# Bpod_Controller_v5.net
KiCad netlist of a schematic drawn in Altium Designer
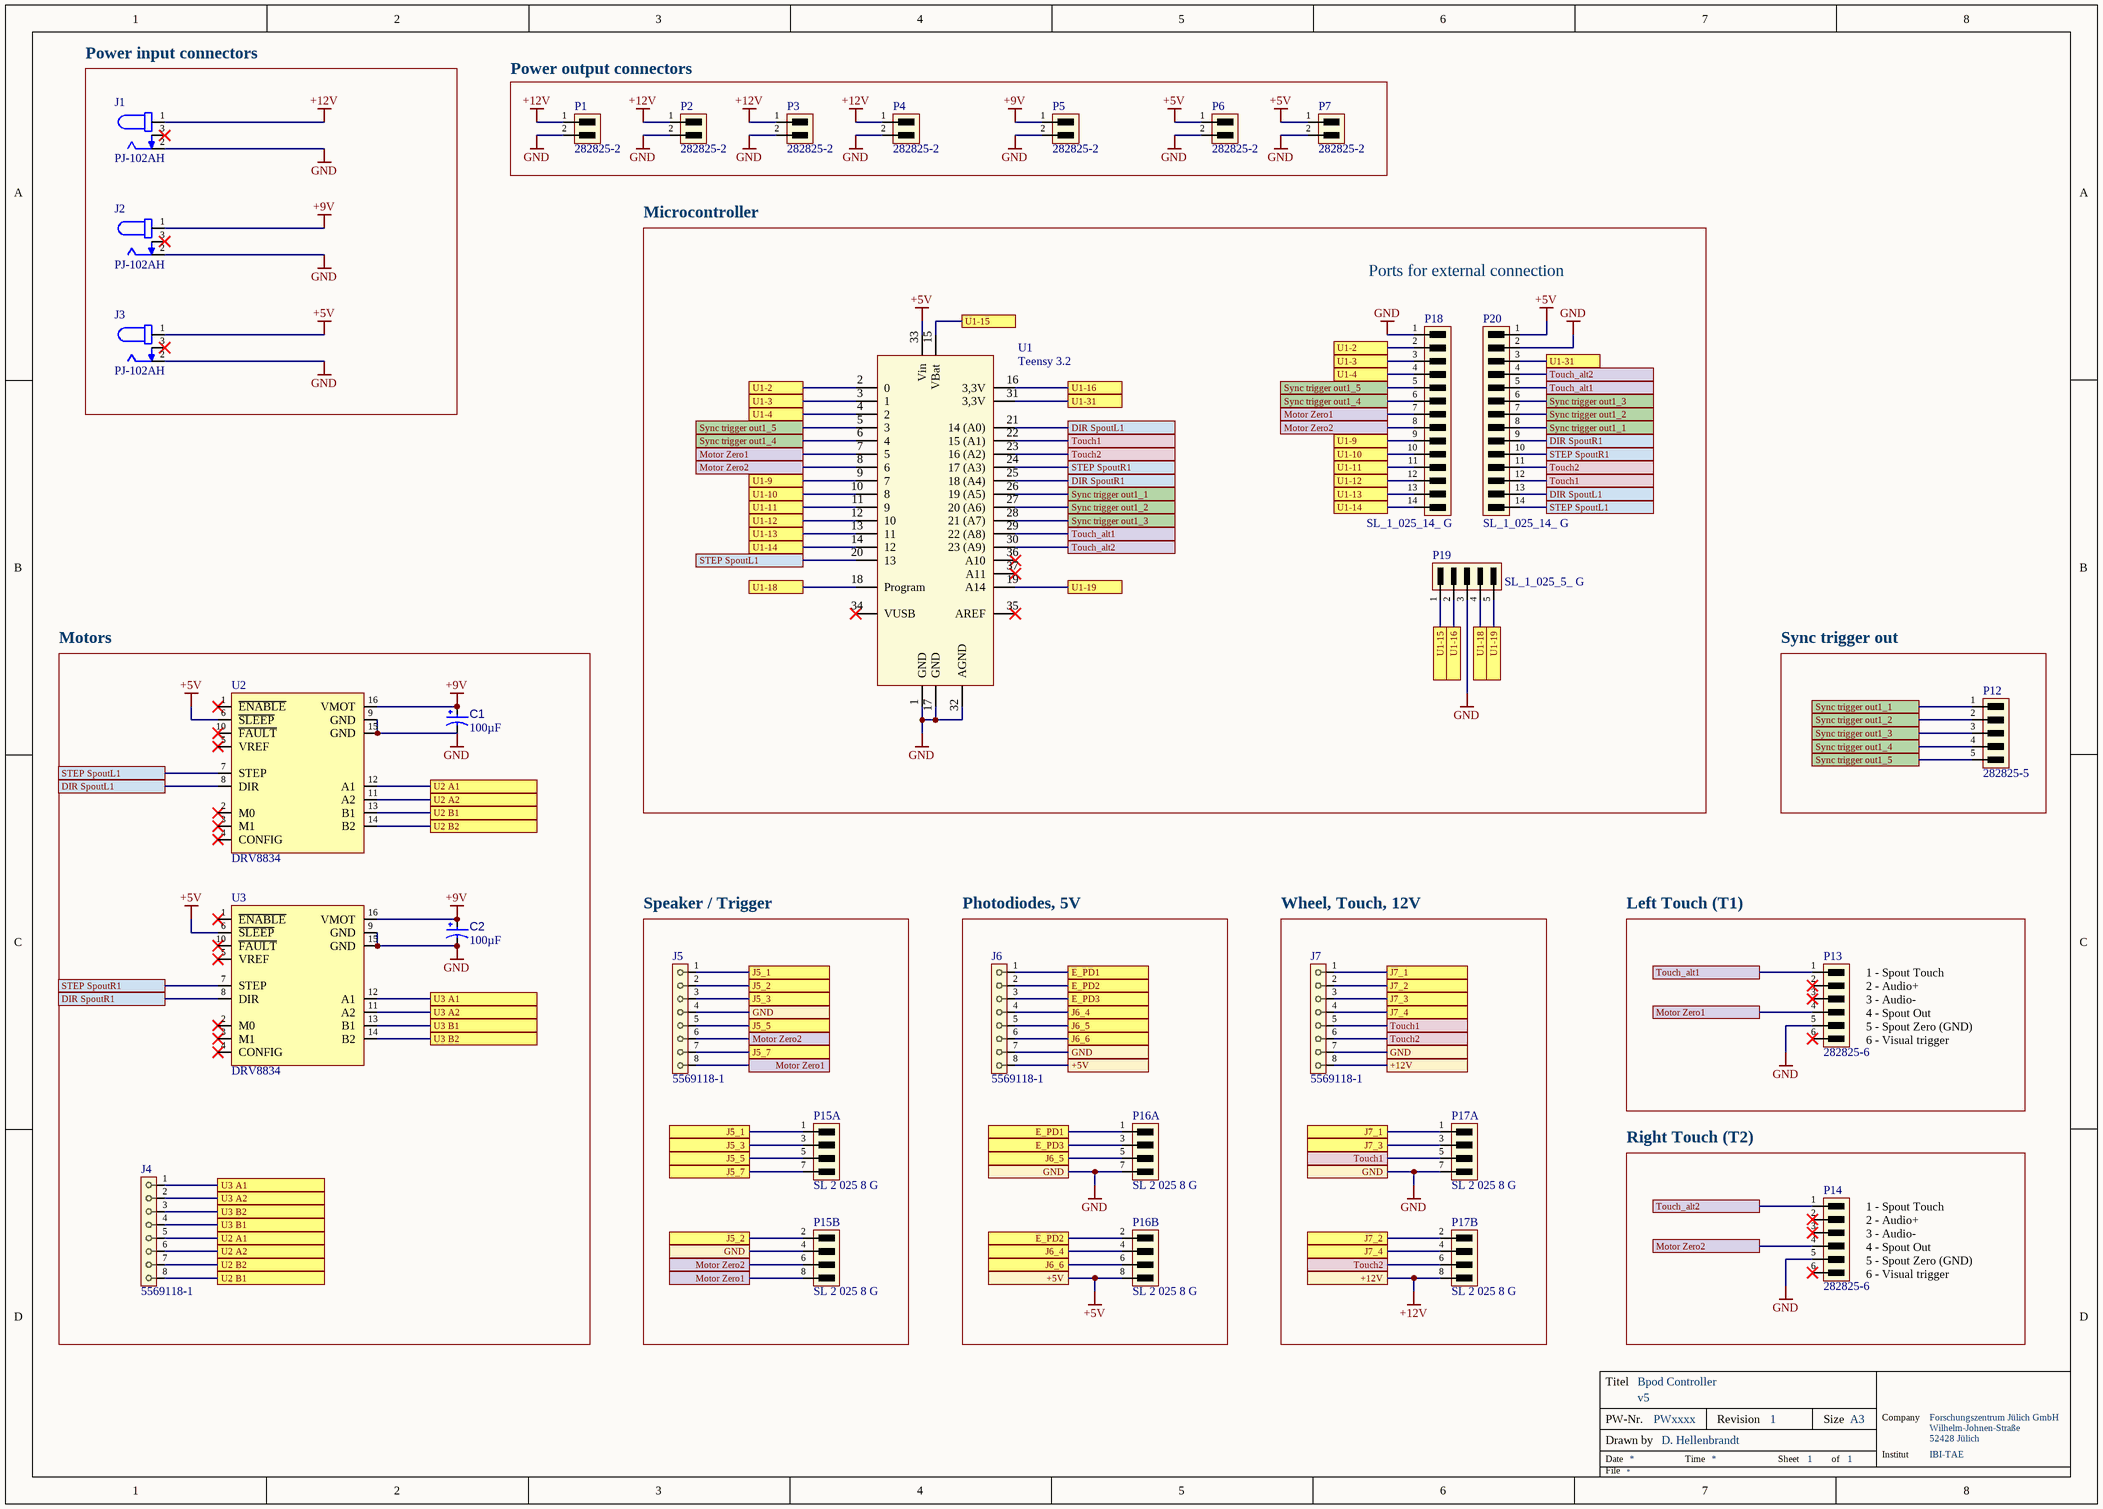
[diagram p0: Bpod_Controller_v5.SchDoc]

(export (version "E")
  (design (tool "Eeschema 10.0.6"))
  (components
    (comp (ref "C1")
      (value "100µF")
      (footprint "AVX-TAJ-C-2_M")
      (description "Standard Tantalum, 100 uF, +/- 10%, 16 V, -55 to 125 degC, 2312 (6032 Metric), RoHS, Tape and Reel")
      (fields (field (name "TOLERANCE") "10%") (field (name "MANUFACTURER") "AVX"))
      (libsource (lib "") (part "CAP-P-2_1"))
    )
    (comp (ref "C2")
      (value "100µF")
      (footprint "AVX-TAJ-C-2_M")
      (description "Standard Tantalum, 100 uF, +/- 10%, 16 V, -55 to 125 degC, 2312 (6032 Metric), RoHS, Tape and Reel")
      (fields (field (name "TOLERANCE") "10%") (field (name "MANUFACTURER") "AVX"))
      (libsource (lib "Forschungszentrum Jülich GmbH") (part "CAP-P-2"))
    )
    (comp (ref "J1")
      (value "PJ-102AH")
      (footprint "CUI_PJ-102AH")
      (description "12V, 2.5A, 2mm Dia")
      (fields (field (name "USER") "IBI-TAE"))
      (libsource (lib "Forschungszentrum Jülich GmbH") (part "PJ-102AH"))
    )
    (comp (ref "J2")
      (value "PJ-102AH")
      (footprint "CUI_PJ-102AH")
      (description "12V, 2.5A, 2mm Dia")
      (fields (field (name "USER") "IBI-TAE"))
      (libsource (lib "Forschungszentrum Jülich GmbH") (part "PJ-102AH"))
    )
    (comp (ref "J3")
      (value "PJ-102AH")
      (footprint "CUI_PJ-102AH")
      (description "12V, 2.5A, 2mm Dia")
      (fields (field (name "USER") "IBI-TAE"))
      (libsource (lib "Forschungszentrum Jülich GmbH") (part "PJ-102AH"))
    )
    (comp (ref "J4")
      (value "5569118-1")
      (footprint "5569118-1-Footprint-1")
      (description "Telecom and Datacom Connector, 8 Contact(s), Female, Right Angle, Solder Terminal, Locking, Jack")
      (fields (field (name "USER") "IBI-TAE"))
      (libsource (lib "Forschungszentrum Jülich GmbH") (part "5569118-1"))
    )
    (comp (ref "J5")
      (value "5569118-1")
      (footprint "5569118-1-Footprint-1")
      (description "Telecom and Datacom Connector, 8 Contact(s), Female, Right Angle, Solder Terminal, Locking, Jack")
      (fields (field (name "USER") "IBI-TAE"))
      (libsource (lib "Forschungszentrum Jülich GmbH") (part "5569118-1"))
    )
    (comp (ref "J6")
      (value "5569118-1")
      (footprint "5569118-1-Footprint-1")
      (description "Telecom and Datacom Connector, 8 Contact(s), Female, Right Angle, Solder Terminal, Locking, Jack")
      (fields (field (name "USER") "IBI-TAE"))
      (libsource (lib "Forschungszentrum Jülich GmbH") (part "5569118-1"))
    )
    (comp (ref "J7")
      (value "5569118-1")
      (footprint "5569118-1-Footprint-1")
      (description "Telecom and Datacom Connector, 8 Contact(s), Female, Right Angle, Solder Terminal, Locking, Jack")
      (fields (field (name "USER") "IBI-TAE"))
      (libsource (lib "Forschungszentrum Jülich GmbH") (part "5569118-1"))
    )
    (comp (ref "P1")
      (value "282825-2")
      (footprint "282825-4-Footprint-1")
      (description "Strip Terminal Block, 15A, 1 Row(s), 1 Deck(s)")
      (fields (field (name "USER") "IBI-TAE"))
      (libsource (lib "Forschungszentrum Jülich GmbH") (part "282825-2"))
    )
    (comp (ref "P2")
      (value "282825-2")
      (footprint "282825-4-Footprint-1")
      (description "Strip Terminal Block, 15A, 1 Row(s), 1 Deck(s)")
      (fields (field (name "USER") "IBI-TAE"))
      (libsource (lib "Forschungszentrum Jülich GmbH") (part "282825-2"))
    )
    (comp (ref "P3")
      (value "282825-2")
      (footprint "282825-4-Footprint-1")
      (description "Strip Terminal Block, 15A, 1 Row(s), 1 Deck(s)")
      (fields (field (name "USER") "IBI-TAE"))
      (libsource (lib "Forschungszentrum Jülich GmbH") (part "282825-2"))
    )
    (comp (ref "P4")
      (value "282825-2")
      (footprint "282825-4-Footprint-1")
      (description "Strip Terminal Block, 15A, 1 Row(s), 1 Deck(s)")
      (fields (field (name "USER") "IBI-TAE"))
      (libsource (lib "Forschungszentrum Jülich GmbH") (part "282825-2"))
    )
    (comp (ref "P5")
      (value "282825-2")
      (footprint "282825-4-Footprint-1")
      (description "Strip Terminal Block, 15A, 1 Row(s), 1 Deck(s)")
      (fields (field (name "USER") "IBI-TAE"))
      (libsource (lib "Forschungszentrum Jülich GmbH") (part "282825-2"))
    )
    (comp (ref "P6")
      (value "282825-2")
      (footprint "282825-4-Footprint-1")
      (description "Strip Terminal Block, 15A, 1 Row(s), 1 Deck(s)")
      (fields (field (name "USER") "IBI-TAE"))
      (libsource (lib "Forschungszentrum Jülich GmbH") (part "282825-2"))
    )
    (comp (ref "P7")
      (value "282825-2")
      (footprint "282825-4-Footprint-1")
      (description "Strip Terminal Block, 15A, 1 Row(s), 1 Deck(s)")
      (fields (field (name "USER") "IBI-TAE"))
      (libsource (lib "Forschungszentrum Jülich GmbH") (part "282825-2"))
    )
    (comp (ref "P12")
      (value "282825-5")
      (footprint "282825-4-Footprint-1")
      (description "Strip Terminal Block, 15A, 1 Row(s), 1 Deck(s)")
      (fields (field (name "USER") "IBI-TAE"))
      (libsource (lib "Forschungszentrum Jülich GmbH") (part "282825-5"))
    )
    (comp (ref "P13")
      (value "282825-6")
      (footprint "282825-4-Footprint-1")
      (description "Strip Terminal Block, 15A, 1 Row(s), 1 Deck(s)")
      (fields (field (name "USER") "IBI-TAE"))
      (libsource (lib "Forschungszentrum Jülich GmbH") (part "282825-6"))
    )
    (comp (ref "P14")
      (value "282825-6")
      (footprint "282825-4-Footprint-1")
      (description "Strip Terminal Block, 15A, 1 Row(s), 1 Deck(s)")
      (fields (field (name "USER") "IBI-TAE"))
      (libsource (lib "Forschungszentrum Jülich GmbH") (part "282825-6"))
    )
    (comp (ref "P15")
      (value "SL 2 025 8 G")
      (footprint "SL 2 025 2 G-Footprint-1")
      (description "Fischer  SL 2 025 8 G, Stiftleiste, 2 Reiheb, 8 Pole, vergoldet")
      (fields (field (name "USER") "IBI-TAE"))
      (libsource (lib "Forschungszentrum Jülich GmbH") (part "SL 2 025 8 G"))
    )
    (comp (ref "P16")
      (value "SL 2 025 8 G")
      (footprint "SL 2 025 2 G-Footprint-1")
      (description "Fischer  SL 2 025 8 G, Stiftleiste, 2 Reiheb, 8 Pole, vergoldet")
      (fields (field (name "USER") "IBI-TAE"))
      (libsource (lib "") (part "SL 2 025 8 G_1"))
    )
    (comp (ref "P17")
      (value "SL 2 025 8 G")
      (footprint "SL 2 025 2 G-Footprint-1")
      (description "Fischer  SL 2 025 8 G, Stiftleiste, 2 Reiheb, 8 Pole, vergoldet")
      (fields (field (name "USER") "IBI-TAE"))
      (libsource (lib "Forschungszentrum Jülich GmbH") (part "SL 2 025 8 G"))
    )
    (comp (ref "P18")
      (value "SL_1_025_14_ G")
      (footprint "SL_1_025_14_ G")
      (description "Fischer SL_1_025_14_ G, Stiftleiste, 1 Reiheb, 14 Pole, vergoldet")
      (fields (field (name "USER") "IBI-TAE"))
      (libsource (lib "Forschungszentrum Jülich GmbH") (part "SL_1_025_14_ G"))
    )
    (comp (ref "P19")
      (value "SL_1_025_5_ G")
      (footprint "SL_1_025_5_ G")
      (description "Fischer SL_1_025_5_ G, Stiftleiste, 1 Reiheb, 5 Pole, vergoldet")
      (fields (field (name "USER") "IBI-TAE"))
      (libsource (lib "Forschungszentrum Jülich GmbH") (part "SL_1_025_5_ G"))
    )
    (comp (ref "P20")
      (value "SL_1_025_14_ G")
      (footprint "SL_1_025_14_ G")
      (description "Fischer SL_1_025_14_ G, Stiftleiste, 1 Reiheb, 14 Pole, vergoldet")
      (fields (field (name "USER") "IBI-TAE"))
      (libsource (lib "") (part "SL_1_025_14_ G_1"))
    )
    (comp (ref "U1")
      (value "Teensy 3.2")
      (footprint "New footprint 1")
      (description "Development Boards & Kits, ARM Teensy 3.2 and header")
      (fields (field (name "USER") "IBI-TAE"))
      (libsource (lib "Forschungszentrum Jülich GmbH") (part "Teensy 3,2"))
    )
    (comp (ref "U2")
      (value "DRV8834")
      (footprint "DRV8825 STEPPER MOTOR DRIVER CARRIER-Footprint-1")
      (description "DRV8834 Low-Voltage Stepper Motor Driver Carrier")
      (fields (field (name "USER") "IBI-TAE"))
      (libsource (lib "Forschungszentrum Jülich GmbH") (part "Pololu DRV8834"))
    )
    (comp (ref "U3")
      (value "DRV8834")
      (footprint "DRV8825 STEPPER MOTOR DRIVER CARRIER-Footprint-1")
      (description "DRV8834 Low-Voltage Stepper Motor Driver Carrier")
      (fields (field (name "USER") "IBI-TAE"))
      (libsource (lib "Forschungszentrum Jülich GmbH") (part "Pololu DRV8834"))
    )
  )
  (nets
    (net (code "1") (name "+5V") (class "Default")
      (node (ref "J3") (pin "1") (pinfunction "1_1") (pintype "passive"))
      (node (ref "J6") (pin "8") (pinfunction "8_8") (pintype "passive"))
      (node (ref "P16") (pin "8") (pinfunction "8_8") (pintype "passive"))
      (node (ref "P20") (pin "1") (pinfunction "1_1") (pintype "passive"))
      (node (ref "P6") (pin "1") (pinfunction "1_1") (pintype "passive"))
      (node (ref "P7") (pin "1") (pinfunction "1_1") (pintype "passive"))
      (node (ref "U1") (pin "33") (pinfunction "Vin_33") (pintype "power_in"))
      (node (ref "U2") (pin "6") (pinfunction "~{SLEEP}_6") (pintype "passive"))
      (node (ref "U3") (pin "6") (pinfunction "~{SLEEP}_6") (pintype "passive"))
    )
    (net (code "2") (name "+9V") (class "Default")
      (node (ref "C1") (pin "1") (pinfunction "1_1") (pintype "passive"))
      (node (ref "C2") (pin "1") (pinfunction "1_1") (pintype "passive"))
      (node (ref "J2") (pin "1") (pinfunction "1_1") (pintype "passive"))
      (node (ref "P5") (pin "1") (pinfunction "1_1") (pintype "passive"))
      (node (ref "U2") (pin "16") (pinfunction "VMOT_16") (pintype "passive"))
      (node (ref "U3") (pin "16") (pinfunction "VMOT_16") (pintype "passive"))
    )
    (net (code "3") (name "+12V") (class "Default")
      (node (ref "J1") (pin "1") (pinfunction "1_1") (pintype "passive"))
      (node (ref "J7") (pin "8") (pinfunction "8_8") (pintype "passive"))
      (node (ref "P1") (pin "1") (pinfunction "1_1") (pintype "passive"))
      (node (ref "P17") (pin "8") (pinfunction "8_8") (pintype "passive"))
      (node (ref "P2") (pin "1") (pinfunction "1_1") (pintype "passive"))
      (node (ref "P3") (pin "1") (pinfunction "1_1") (pintype "passive"))
      (node (ref "P4") (pin "1") (pinfunction "1_1") (pintype "passive"))
    )
    (net (code "4") (name "/DIR SpoutL1") (class "Default")
      (node (ref "P20") (pin "13") (pinfunction "13_13") (pintype "passive"))
      (node (ref "U1") (pin "21") (pinfunction "14_(A0)_21") (pintype "passive"))
      (node (ref "U2") (pin "8") (pinfunction "DIR_8") (pintype "passive"))
    )
    (net (code "5") (name "/DIR SpoutR1") (class "Default")
      (node (ref "P20") (pin "9") (pinfunction "9_9") (pintype "passive"))
      (node (ref "U1") (pin "25") (pinfunction "18_(A4)_25") (pintype "passive"))
      (node (ref "U3") (pin "8") (pinfunction "DIR_8") (pintype "passive"))
    )
    (net (code "6") (name "/E_PD1") (class "Default")
      (node (ref "J6") (pin "1") (pinfunction "1_1") (pintype "passive"))
      (node (ref "P16") (pin "1") (pinfunction "1_1") (pintype "passive"))
    )
    (net (code "7") (name "/E_PD2") (class "Default")
      (node (ref "J6") (pin "2") (pinfunction "2_2") (pintype "passive"))
      (node (ref "P16") (pin "2") (pinfunction "2_2") (pintype "passive"))
    )
    (net (code "8") (name "/E_PD3") (class "Default")
      (node (ref "J6") (pin "3") (pinfunction "3_3") (pintype "passive"))
      (node (ref "P16") (pin "3") (pinfunction "3_3") (pintype "passive"))
    )
    (net (code "9") (name "/J5_1") (class "Default")
      (node (ref "J5") (pin "1") (pinfunction "1_1") (pintype "passive"))
      (node (ref "P15") (pin "1") (pinfunction "1_1") (pintype "passive"))
    )
    (net (code "10") (name "/J5_2") (class "Default")
      (node (ref "J5") (pin "2") (pinfunction "2_2") (pintype "passive"))
      (node (ref "P15") (pin "2") (pinfunction "2_2") (pintype "passive"))
    )
    (net (code "11") (name "/J5_3") (class "Default")
      (node (ref "J5") (pin "3") (pinfunction "3_3") (pintype "passive"))
      (node (ref "P15") (pin "3") (pinfunction "3_3") (pintype "passive"))
    )
    (net (code "12") (name "/J5_5") (class "Default")
      (node (ref "J5") (pin "5") (pinfunction "5_5") (pintype "passive"))
      (node (ref "P15") (pin "5") (pinfunction "5_5") (pintype "passive"))
    )
    (net (code "13") (name "/J5_7") (class "Default")
      (node (ref "J5") (pin "7") (pinfunction "7_7") (pintype "passive"))
      (node (ref "P15") (pin "7") (pinfunction "7_7") (pintype "passive"))
    )
    (net (code "14") (name "/J6_4") (class "Default")
      (node (ref "J6") (pin "4") (pinfunction "4_4") (pintype "passive"))
      (node (ref "P16") (pin "4") (pinfunction "4_4") (pintype "passive"))
    )
    (net (code "15") (name "/J6_5") (class "Default")
      (node (ref "J6") (pin "5") (pinfunction "5_5") (pintype "passive"))
      (node (ref "P16") (pin "5") (pinfunction "5_5") (pintype "passive"))
    )
    (net (code "16") (name "/J6_6") (class "Default")
      (node (ref "J6") (pin "6") (pinfunction "6_6") (pintype "passive"))
      (node (ref "P16") (pin "6") (pinfunction "6_6") (pintype "passive"))
    )
    (net (code "17") (name "/J7_1") (class "Default")
      (node (ref "J7") (pin "1") (pinfunction "1_1") (pintype "passive"))
      (node (ref "P17") (pin "1") (pinfunction "1_1") (pintype "passive"))
    )
    (net (code "18") (name "/J7_2") (class "Default")
      (node (ref "J7") (pin "2") (pinfunction "2_2") (pintype "passive"))
      (node (ref "P17") (pin "2") (pinfunction "2_2") (pintype "passive"))
    )
    (net (code "19") (name "/J7_3") (class "Default")
      (node (ref "J7") (pin "3") (pinfunction "3_3") (pintype "passive"))
      (node (ref "P17") (pin "3") (pinfunction "3_3") (pintype "passive"))
    )
    (net (code "20") (name "/J7_4") (class "Default")
      (node (ref "J7") (pin "4") (pinfunction "4_4") (pintype "passive"))
      (node (ref "P17") (pin "4") (pinfunction "4_4") (pintype "passive"))
    )
    (net (code "21") (name "/Motor Zero1") (class "Default")
      (node (ref "J5") (pin "8") (pinfunction "8_8") (pintype "passive"))
      (node (ref "P13") (pin "4") (pinfunction "4_4") (pintype "passive"))
      (node (ref "P15") (pin "8") (pinfunction "8_8") (pintype "passive"))
      (node (ref "P18") (pin "7") (pinfunction "7_7") (pintype "passive"))
      (node (ref "U1") (pin "7") (pinfunction "5_7") (pintype "passive"))
    )
    (net (code "22") (name "/Motor Zero2") (class "Default")
      (node (ref "J5") (pin "6") (pinfunction "6_6") (pintype "passive"))
      (node (ref "P14") (pin "4") (pinfunction "4_4") (pintype "passive"))
      (node (ref "P15") (pin "6") (pinfunction "6_6") (pintype "passive"))
      (node (ref "P18") (pin "8") (pinfunction "8_8") (pintype "passive"))
      (node (ref "U1") (pin "8") (pinfunction "6_8") (pintype "passive"))
    )
    (net (code "23") (name "/STEP SpoutL1") (class "Default")
      (node (ref "P20") (pin "14") (pinfunction "14_14") (pintype "passive"))
      (node (ref "U1") (pin "20") (pinfunction "13_20") (pintype "passive"))
      (node (ref "U2") (pin "7") (pinfunction "STEP_7") (pintype "passive"))
    )
    (net (code "24") (name "/STEP SpoutR1") (class "Default")
      (node (ref "P20") (pin "10") (pinfunction "10_10") (pintype "passive"))
      (node (ref "U1") (pin "24") (pinfunction "17_(A3)_24") (pintype "passive"))
      (node (ref "U3") (pin "7") (pinfunction "STEP_7") (pintype "passive"))
    )
    (net (code "25") (name "/Sync trigger out1_1") (class "Default")
      (node (ref "P12") (pin "1") (pinfunction "1_1") (pintype "passive"))
      (node (ref "P20") (pin "8") (pinfunction "8_8") (pintype "passive"))
      (node (ref "U1") (pin "26") (pinfunction "19_(A5)_26") (pintype "passive"))
    )
    (net (code "26") (name "/Sync trigger out1_2") (class "Default")
      (node (ref "P12") (pin "2") (pinfunction "2_2") (pintype "passive"))
      (node (ref "P20") (pin "7") (pinfunction "7_7") (pintype "passive"))
      (node (ref "U1") (pin "27") (pinfunction "20_(A6)_27") (pintype "passive"))
    )
    (net (code "27") (name "/Sync trigger out1_3") (class "Default")
      (node (ref "P12") (pin "3") (pinfunction "3_3") (pintype "passive"))
      (node (ref "P20") (pin "6") (pinfunction "6_6") (pintype "passive"))
      (node (ref "U1") (pin "28") (pinfunction "21_(A7)_28") (pintype "passive"))
    )
    (net (code "28") (name "/Sync trigger out1_4") (class "Default")
      (node (ref "P12") (pin "4") (pinfunction "4_4") (pintype "passive"))
      (node (ref "P18") (pin "6") (pinfunction "6_6") (pintype "passive"))
      (node (ref "U1") (pin "6") (pinfunction "4_6") (pintype "passive"))
    )
    (net (code "29") (name "/Sync trigger out1_5") (class "Default")
      (node (ref "P12") (pin "5") (pinfunction "5_5") (pintype "passive"))
      (node (ref "P18") (pin "5") (pinfunction "5_5") (pintype "passive"))
      (node (ref "U1") (pin "5") (pinfunction "3_5") (pintype "passive"))
    )
    (net (code "30") (name "/Touch1") (class "Default")
      (node (ref "J7") (pin "5") (pinfunction "5_5") (pintype "passive"))
      (node (ref "P17") (pin "5") (pinfunction "5_5") (pintype "passive"))
      (node (ref "P20") (pin "12") (pinfunction "12_12") (pintype "passive"))
      (node (ref "U1") (pin "22") (pinfunction "15_(A1)_22") (pintype "passive"))
    )
    (net (code "31") (name "/Touch2") (class "Default")
      (node (ref "J7") (pin "6") (pinfunction "6_6") (pintype "passive"))
      (node (ref "P17") (pin "6") (pinfunction "6_6") (pintype "passive"))
      (node (ref "P20") (pin "11") (pinfunction "11_11") (pintype "passive"))
      (node (ref "U1") (pin "23") (pinfunction "16_(A2)_23") (pintype "passive"))
    )
    (net (code "32") (name "/Touch_alt1") (class "Default")
      (node (ref "P13") (pin "1") (pinfunction "1_1") (pintype "passive"))
      (node (ref "P20") (pin "5") (pinfunction "5_5") (pintype "passive"))
      (node (ref "U1") (pin "29") (pinfunction "22_(A8)_29") (pintype "passive"))
    )
    (net (code "33") (name "/Touch_alt2") (class "Default")
      (node (ref "P14") (pin "1") (pinfunction "1_1") (pintype "passive"))
      (node (ref "P20") (pin "4") (pinfunction "4_4") (pintype "passive"))
      (node (ref "U1") (pin "30") (pinfunction "23_(A9)_30") (pintype "passive"))
    )
    (net (code "34") (name "/U1-2") (class "Default")
      (node (ref "P18") (pin "2") (pinfunction "2_2") (pintype "passive"))
      (node (ref "U1") (pin "2") (pinfunction "0_2") (pintype "passive"))
    )
    (net (code "35") (name "/U1-3") (class "Default")
      (node (ref "P18") (pin "3") (pinfunction "3_3") (pintype "passive"))
      (node (ref "U1") (pin "3") (pinfunction "1_3") (pintype "passive"))
    )
    (net (code "36") (name "/U1-4") (class "Default")
      (node (ref "P18") (pin "4") (pinfunction "4_4") (pintype "passive"))
      (node (ref "U1") (pin "4") (pinfunction "2_4") (pintype "passive"))
    )
    (net (code "37") (name "/U1-9") (class "Default")
      (node (ref "P18") (pin "9") (pinfunction "9_9") (pintype "passive"))
      (node (ref "U1") (pin "9") (pinfunction "7_9") (pintype "passive"))
    )
    (net (code "38") (name "/U1-10") (class "Default")
      (node (ref "P18") (pin "10") (pinfunction "10_10") (pintype "passive"))
      (node (ref "U1") (pin "10") (pinfunction "8_10") (pintype "passive"))
    )
    (net (code "39") (name "/U1-11") (class "Default")
      (node (ref "P18") (pin "11") (pinfunction "11_11") (pintype "passive"))
      (node (ref "U1") (pin "11") (pinfunction "9_11") (pintype "passive"))
    )
    (net (code "40") (name "/U1-12") (class "Default")
      (node (ref "P18") (pin "12") (pinfunction "12_12") (pintype "passive"))
      (node (ref "U1") (pin "12") (pinfunction "10_12") (pintype "passive"))
    )
    (net (code "41") (name "/U1-13") (class "Default")
      (node (ref "P18") (pin "13") (pinfunction "13_13") (pintype "passive"))
      (node (ref "U1") (pin "13") (pinfunction "11_13") (pintype "passive"))
    )
    (net (code "42") (name "/U1-14") (class "Default")
      (node (ref "P18") (pin "14") (pinfunction "14_14") (pintype "passive"))
      (node (ref "U1") (pin "14") (pinfunction "12_14") (pintype "passive"))
    )
    (net (code "43") (name "/U1-15") (class "Default")
      (node (ref "P19") (pin "1") (pinfunction "1_1") (pintype "passive"))
      (node (ref "U1") (pin "15") (pinfunction "VBat_15") (pintype "passive"))
    )
    (net (code "44") (name "/U1-16") (class "Default")
      (node (ref "P19") (pin "2") (pinfunction "2_2") (pintype "passive"))
      (node (ref "U1") (pin "16") (pinfunction "3,3V_16") (pintype "passive"))
    )
    (net (code "45") (name "/U1-18") (class "Default")
      (node (ref "P19") (pin "4") (pinfunction "4_4") (pintype "passive"))
      (node (ref "U1") (pin "18") (pinfunction "Program_18") (pintype "passive"))
    )
    (net (code "46") (name "/U1-19") (class "Default")
      (node (ref "P19") (pin "5") (pinfunction "5_5") (pintype "passive"))
      (node (ref "U1") (pin "19") (pinfunction "A14_19") (pintype "passive"))
    )
    (net (code "47") (name "/U1-31") (class "Default")
      (node (ref "P20") (pin "3") (pinfunction "3_3") (pintype "passive"))
      (node (ref "U1") (pin "31") (pinfunction "3,3V_31") (pintype "passive"))
    )
    (net (code "48") (name "/U2 A1") (class "Default")
      (node (ref "J4") (pin "5") (pinfunction "5_5") (pintype "passive"))
      (node (ref "U2") (pin "12") (pinfunction "A1_12") (pintype "passive"))
    )
    (net (code "49") (name "/U2 A2") (class "Default")
      (node (ref "J4") (pin "6") (pinfunction "6_6") (pintype "passive"))
      (node (ref "U2") (pin "11") (pinfunction "A2_11") (pintype "passive"))
    )
    (net (code "50") (name "/U2 B1") (class "Default")
      (node (ref "J4") (pin "8") (pinfunction "8_8") (pintype "passive"))
      (node (ref "U2") (pin "13") (pinfunction "B1_13") (pintype "passive"))
    )
    (net (code "51") (name "/U2 B2") (class "Default")
      (node (ref "J4") (pin "7") (pinfunction "7_7") (pintype "passive"))
      (node (ref "U2") (pin "14") (pinfunction "B2_14") (pintype "passive"))
    )
    (net (code "52") (name "/U3 A1") (class "Default")
      (node (ref "J4") (pin "1") (pinfunction "1_1") (pintype "passive"))
      (node (ref "U3") (pin "12") (pinfunction "A1_12") (pintype "passive"))
    )
    (net (code "53") (name "/U3 A2") (class "Default")
      (node (ref "J4") (pin "2") (pinfunction "2_2") (pintype "passive"))
      (node (ref "U3") (pin "11") (pinfunction "A2_11") (pintype "passive"))
    )
    (net (code "54") (name "/U3 B1") (class "Default")
      (node (ref "J4") (pin "4") (pinfunction "4_4") (pintype "passive"))
      (node (ref "U3") (pin "13") (pinfunction "B1_13") (pintype "passive"))
    )
    (net (code "55") (name "/U3 B2") (class "Default")
      (node (ref "J4") (pin "3") (pinfunction "3_3") (pintype "passive"))
      (node (ref "U3") (pin "14") (pinfunction "B2_14") (pintype "passive"))
    )
    (net (code "56") (name "GND") (class "Default")
      (node (ref "C1") (pin "2") (pinfunction "2_2") (pintype "passive"))
      (node (ref "C2") (pin "2") (pinfunction "2_2") (pintype "passive"))
      (node (ref "J1") (pin "2") (pinfunction "2_2") (pintype "passive"))
      (node (ref "J2") (pin "2") (pinfunction "2_2") (pintype "passive"))
      (node (ref "J3") (pin "2") (pinfunction "2_2") (pintype "passive"))
      (node (ref "J5") (pin "4") (pinfunction "4_4") (pintype "passive"))
      (node (ref "J6") (pin "7") (pinfunction "7_7") (pintype "passive"))
      (node (ref "J7") (pin "7") (pinfunction "7_7") (pintype "passive"))
      (node (ref "P1") (pin "2") (pinfunction "2_2") (pintype "passive"))
      (node (ref "P13") (pin "5") (pinfunction "5_5") (pintype "passive"))
      (node (ref "P14") (pin "5") (pinfunction "5_5") (pintype "passive"))
      (node (ref "P15") (pin "4") (pinfunction "4_4") (pintype "passive"))
      (node (ref "P16") (pin "7") (pinfunction "7_7") (pintype "passive"))
      (node (ref "P17") (pin "7") (pinfunction "7_7") (pintype "passive"))
      (node (ref "P18") (pin "1") (pinfunction "1_1") (pintype "passive"))
      (node (ref "P19") (pin "3") (pinfunction "3_3") (pintype "passive"))
      (node (ref "P2") (pin "2") (pinfunction "2_2") (pintype "passive"))
      (node (ref "P20") (pin "2") (pinfunction "2_2") (pintype "passive"))
      (node (ref "P3") (pin "2") (pinfunction "2_2") (pintype "passive"))
      (node (ref "P4") (pin "2") (pinfunction "2_2") (pintype "passive"))
      (node (ref "P5") (pin "2") (pinfunction "2_2") (pintype "passive"))
      (node (ref "P6") (pin "2") (pinfunction "2_2") (pintype "passive"))
      (node (ref "P7") (pin "2") (pinfunction "2_2") (pintype "passive"))
      (node (ref "U1") (pin "1") (pinfunction "GND_1") (pintype "passive"))
      (node (ref "U1") (pin "17") (pinfunction "GND_17") (pintype "passive"))
      (node (ref "U1") (pin "32") (pinfunction "AGND_32") (pintype "passive"))
      (node (ref "U2") (pin "15") (pinfunction "GND_15") (pintype "passive"))
      (node (ref "U2") (pin "9") (pinfunction "GND_9") (pintype "passive"))
      (node (ref "U3") (pin "15") (pinfunction "GND_15") (pintype "passive"))
      (node (ref "U3") (pin "9") (pinfunction "GND_9") (pintype "passive"))
    )
    (net (code "57") (name "unconnected-(J1-Pad3)") (class "Default")
      (node (ref "J1") (pin "3") (pinfunction "3_3") (pintype "passive"))
    )
    (net (code "58") (name "unconnected-(J2-Pad3)") (class "Default")
      (node (ref "J2") (pin "3") (pinfunction "3_3") (pintype "passive+no_connect"))
    )
    (net (code "59") (name "unconnected-(J3-Pad3)") (class "Default")
      (node (ref "J3") (pin "3") (pinfunction "3_3") (pintype "passive+no_connect"))
    )
    (net (code "60") (name "unconnected-(P13-Pad2)") (class "Default")
      (node (ref "P13") (pin "2") (pinfunction "2_2") (pintype "passive+no_connect"))
    )
    (net (code "61") (name "unconnected-(P13-Pad3)") (class "Default")
      (node (ref "P13") (pin "3") (pinfunction "3_3") (pintype "passive+no_connect"))
    )
    (net (code "62") (name "unconnected-(P13-Pad6)") (class "Default")
      (node (ref "P13") (pin "6") (pinfunction "6_6") (pintype "passive+no_connect"))
    )
    (net (code "63") (name "unconnected-(P14-Pad2)") (class "Default")
      (node (ref "P14") (pin "2") (pinfunction "2_2") (pintype "passive+no_connect"))
    )
    (net (code "64") (name "unconnected-(P14-Pad3)") (class "Default")
      (node (ref "P14") (pin "3") (pinfunction "3_3") (pintype "passive+no_connect"))
    )
    (net (code "65") (name "unconnected-(P14-Pad6)") (class "Default")
      (node (ref "P14") (pin "6") (pinfunction "6_6") (pintype "passive+no_connect"))
    )
    (net (code "66") (name "unconnected-(U1-A10-Pad36)") (class "Default")
      (node (ref "U1") (pin "36") (pinfunction "A10_36") (pintype "passive+no_connect"))
    )
    (net (code "67") (name "unconnected-(U1-A11-Pad37)") (class "Default")
      (node (ref "U1") (pin "37") (pinfunction "A11_37") (pintype "passive+no_connect"))
    )
    (net (code "68") (name "unconnected-(U1-AREF-Pad35)") (class "Default")
      (node (ref "U1") (pin "35") (pinfunction "AREF_35") (pintype "passive+no_connect"))
    )
    (net (code "69") (name "unconnected-(U1-VUSB-Pad34)") (class "Default")
      (node (ref "U1") (pin "34") (pinfunction "VUSB_34") (pintype "passive+no_connect"))
    )
    (net (code "70") (name "unconnected-(U2-CONFIG-Pad4)") (class "Default")
      (node (ref "U2") (pin "4") (pinfunction "CONFIG_4") (pintype "passive+no_connect"))
    )
    (net (code "71") (name "unconnected-(U2-M0-Pad2)") (class "Default")
      (node (ref "U2") (pin "2") (pinfunction "M0_2") (pintype "passive+no_connect"))
    )
    (net (code "72") (name "unconnected-(U2-M1-Pad3)") (class "Default")
      (node (ref "U2") (pin "3") (pinfunction "M1_3") (pintype "passive+no_connect"))
    )
    (net (code "73") (name "unconnected-(U2-VREF-Pad5)") (class "Default")
      (node (ref "U2") (pin "5") (pinfunction "VREF_5") (pintype "passive+no_connect"))
    )
    (net (code "74") (name "unconnected-(U2-~{ENABLE}-Pad1)") (class "Default")
      (node (ref "U2") (pin "1") (pinfunction "~{ENABLE}_1") (pintype "passive+no_connect"))
    )
    (net (code "75") (name "unconnected-(U2-~{FAULT}-Pad10)") (class "Default")
      (node (ref "U2") (pin "10") (pinfunction "~{FAULT}_10") (pintype "passive+no_connect"))
    )
    (net (code "76") (name "unconnected-(U3-CONFIG-Pad4)") (class "Default")
      (node (ref "U3") (pin "4") (pinfunction "CONFIG_4") (pintype "passive+no_connect"))
    )
    (net (code "77") (name "unconnected-(U3-M0-Pad2)") (class "Default")
      (node (ref "U3") (pin "2") (pinfunction "M0_2") (pintype "passive+no_connect"))
    )
    (net (code "78") (name "unconnected-(U3-M1-Pad3)") (class "Default")
      (node (ref "U3") (pin "3") (pinfunction "M1_3") (pintype "passive+no_connect"))
    )
    (net (code "79") (name "unconnected-(U3-VREF-Pad5)") (class "Default")
      (node (ref "U3") (pin "5") (pinfunction "VREF_5") (pintype "passive+no_connect"))
    )
    (net (code "80") (name "unconnected-(U3-~{ENABLE}-Pad1)") (class "Default")
      (node (ref "U3") (pin "1") (pinfunction "~{ENABLE}_1") (pintype "passive+no_connect"))
    )
    (net (code "81") (name "unconnected-(U3-~{FAULT}-Pad10)") (class "Default")
      (node (ref "U3") (pin "10") (pinfunction "~{FAULT}_10") (pintype "passive+no_connect"))
    )
  )
)
